# schematic.net
KiCad netlist of a schematic drawn in EasyEDA
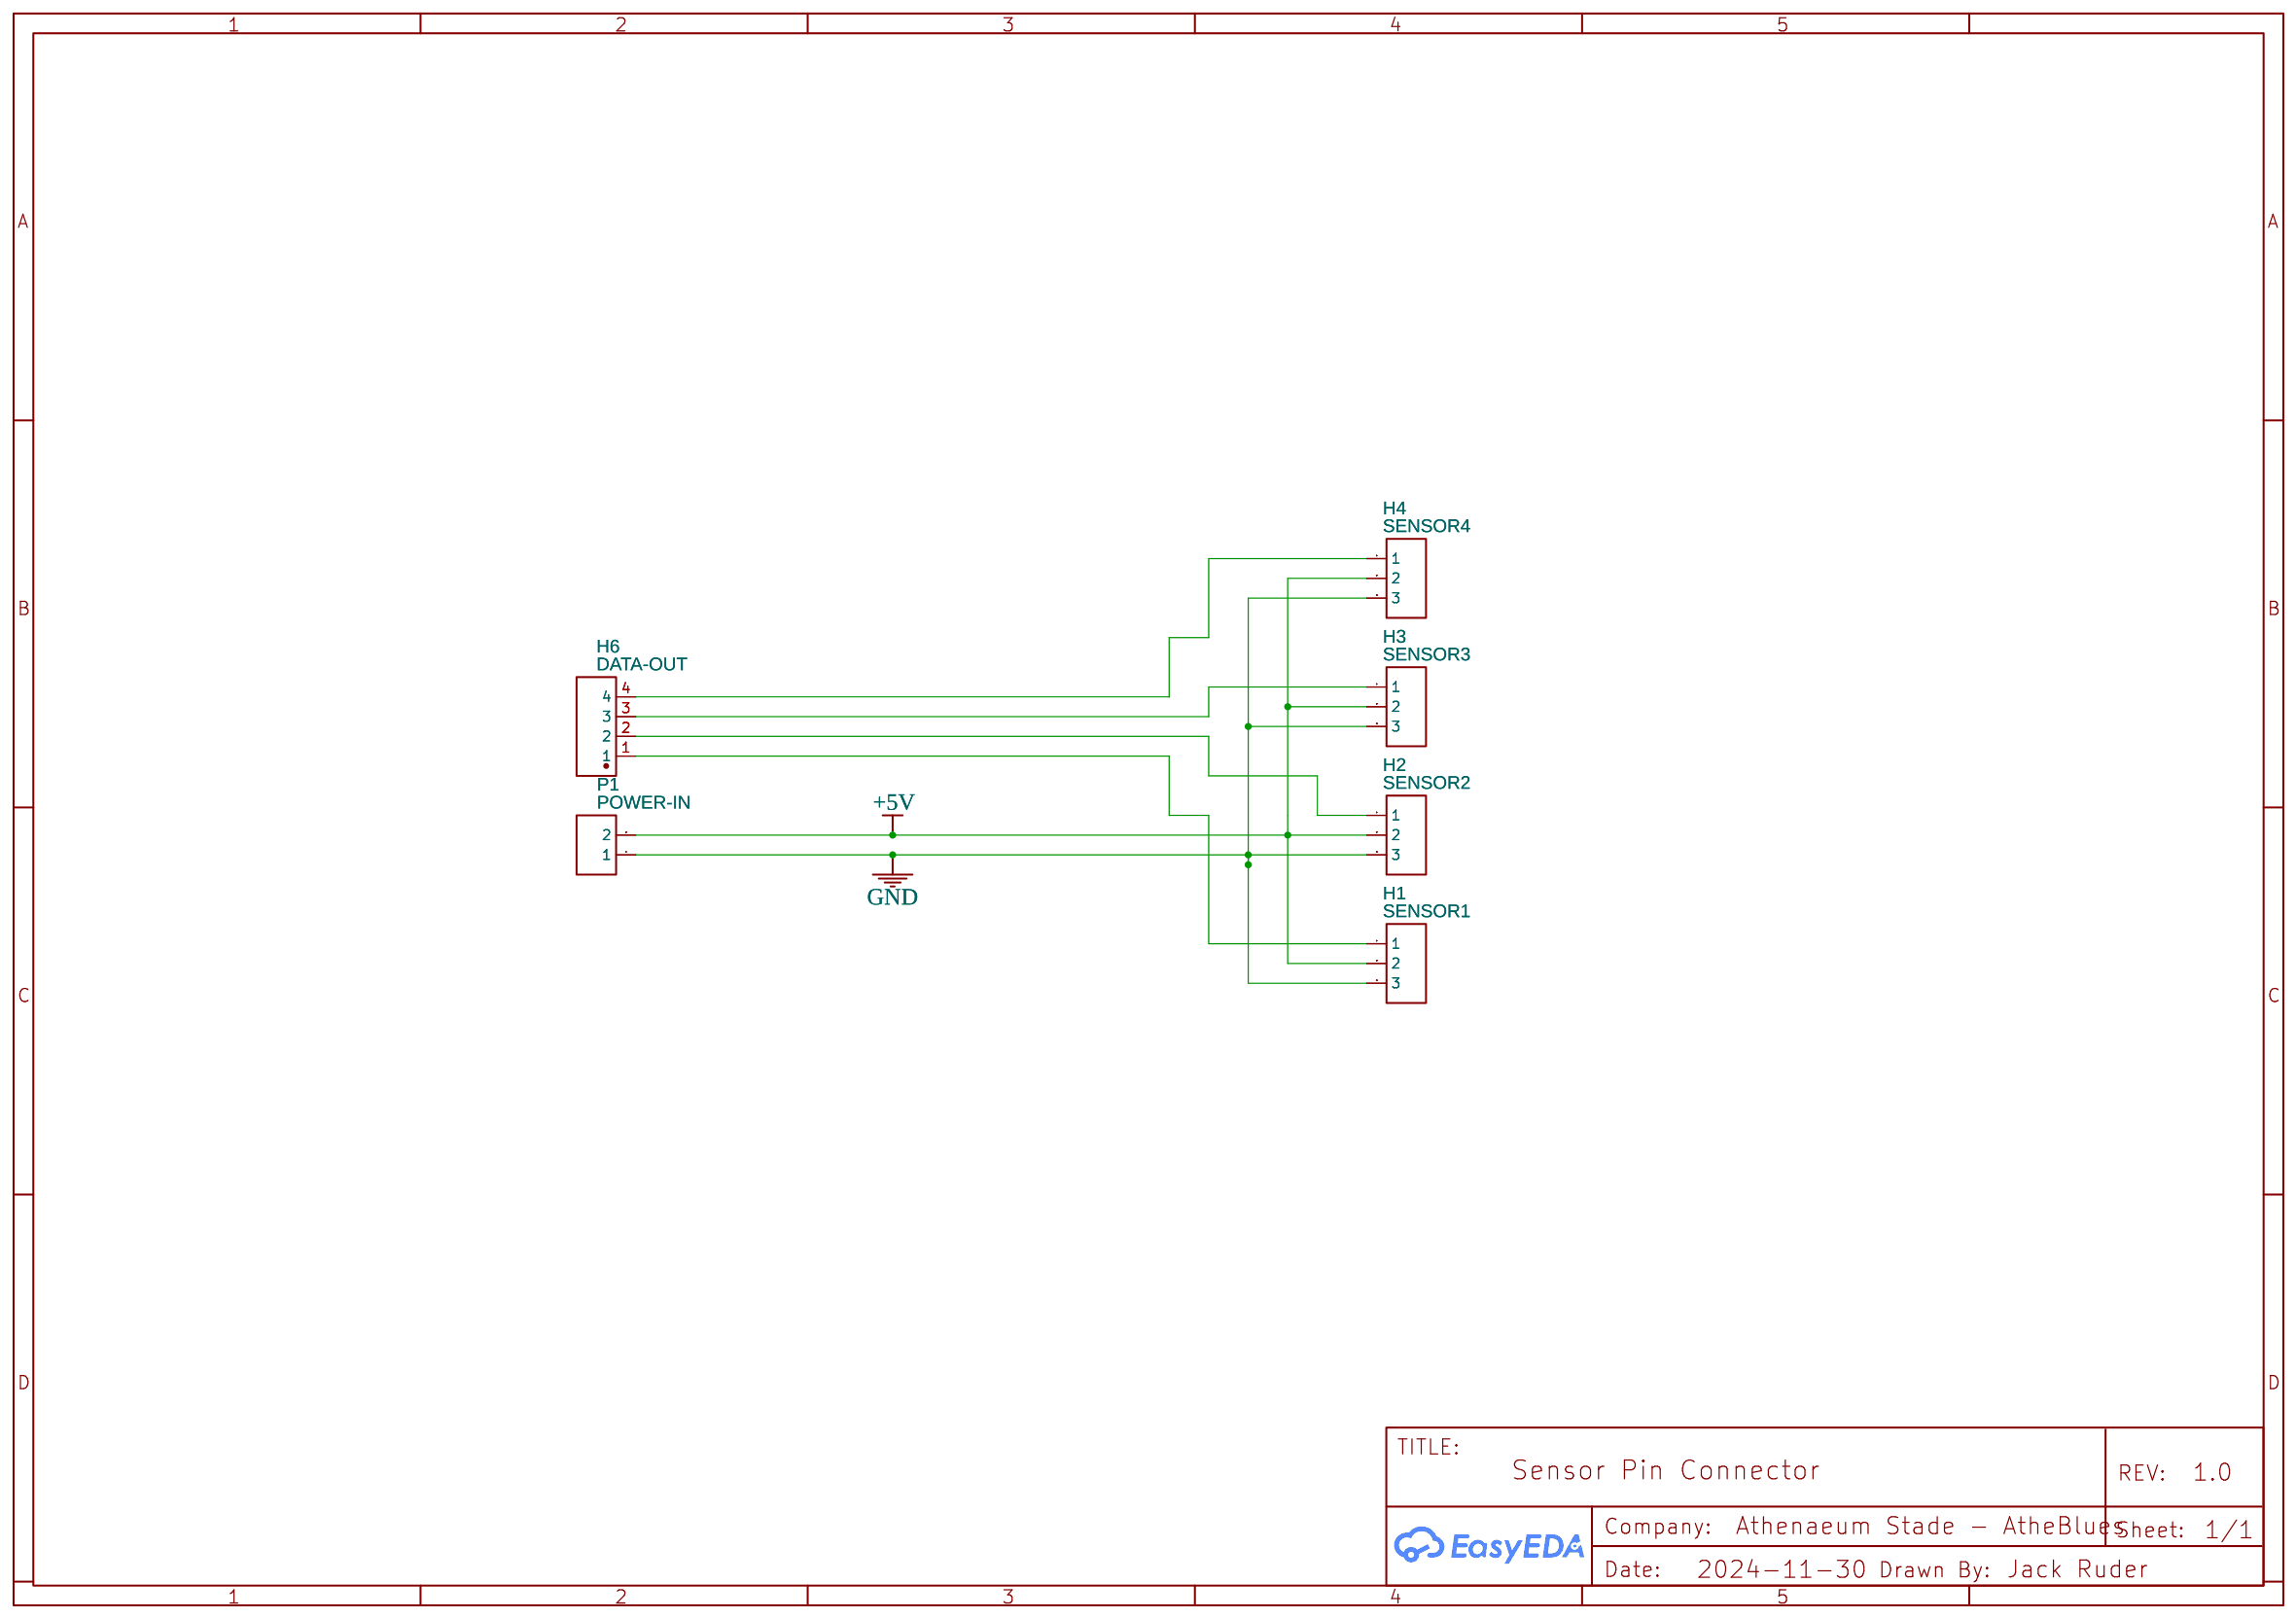
[diagram p0: schematic sheet]

(export (version "E")
  (design (tool "Eeschema 10.0.6"))
  (components
    (comp (ref "H1")
      (value "SENSOR1")
      (fields (field (name "Manufacturer Part") "2.54-1*3P针") (field (name "Manufacturer") "BOOMELE(博穆精密)"))
      (libsource (lib "") (part "Header-Male-2.54_1x3"))
    )
    (comp (ref "H2")
      (value "SENSOR2")
      (fields (field (name "Manufacturer Part") "2.54-1*3P针") (field (name "Manufacturer") "BOOMELE(博穆精密)"))
      (libsource (lib "") (part "Header-Male-2.54_1x3"))
    )
    (comp (ref "H3")
      (value "SENSOR3")
      (fields (field (name "Manufacturer Part") "2.54-1*3P针") (field (name "Manufacturer") "BOOMELE(博穆精密)"))
      (libsource (lib "") (part "Header-Male-2.54_1x3"))
    )
    (comp (ref "H4")
      (value "SENSOR4")
      (fields (field (name "Manufacturer Part") "2.54-1*3P针") (field (name "Manufacturer") "BOOMELE(博穆精密)"))
      (libsource (lib "") (part "Header-Male-2.54_1x3"))
    )
    (comp (ref "H6")
      (value "DATA-OUT")
      (fields (field (name "Manufacturer Part") "PM254V-11-04-H85") (field (name "Manufacturer") "XFCN(兴飞)"))
      (libsource (lib "") (part "PM254V-11-04-H85"))
    )
    (comp (ref "P1")
      (value "POWER-IN")
      (fields (field (name "Manufacturer Part") "2.54-1*2P母") (field (name "Manufacturer") "BOOMELE(博穆精密)"))
      (libsource (lib "") (part "Header-Female-2.54_1x2"))
    )
  )
  (nets
    (net (code "1") (name "+5V") (class "Default")
      (node (ref "H1") (pin "2") (pinfunction "2_2") (pintype "input"))
      (node (ref "H2") (pin "2") (pinfunction "2_2") (pintype "input"))
      (node (ref "H3") (pin "2") (pinfunction "2_2") (pintype "input"))
      (node (ref "H4") (pin "2") (pinfunction "2_2") (pintype "input"))
      (node (ref "P1") (pin "2") (pinfunction "2_2") (pintype "input"))
    )
    (net (code "2") (name "GND") (class "Default")
      (node (ref "H1") (pin "3") (pinfunction "3_3") (pintype "input"))
      (node (ref "H2") (pin "3") (pinfunction "3_3") (pintype "input"))
      (node (ref "H3") (pin "3") (pinfunction "3_3") (pintype "input"))
      (node (ref "H4") (pin "3") (pinfunction "3_3") (pintype "input"))
      (node (ref "P1") (pin "1") (pinfunction "1_1") (pintype "input"))
    )
    (net (code "3") (name "Net-(H1-Pad1)") (class "Default")
      (node (ref "H1") (pin "1") (pinfunction "1_1") (pintype "input"))
      (node (ref "H6") (pin "1") (pinfunction "1_1") (pintype "unspecified"))
    )
    (net (code "4") (name "Net-(H2-Pad1)") (class "Default")
      (node (ref "H2") (pin "1") (pinfunction "1_1") (pintype "input"))
      (node (ref "H6") (pin "2") (pinfunction "2_2") (pintype "unspecified"))
    )
    (net (code "5") (name "Net-(H3-Pad1)") (class "Default")
      (node (ref "H3") (pin "1") (pinfunction "1_1") (pintype "input"))
      (node (ref "H6") (pin "3") (pinfunction "3_3") (pintype "unspecified"))
    )
    (net (code "6") (name "Net-(H4-Pad1)") (class "Default")
      (node (ref "H4") (pin "1") (pinfunction "1_1") (pintype "input"))
      (node (ref "H6") (pin "4") (pinfunction "4_4") (pintype "unspecified"))
    )
  )
)
